# 15_-_MISC_JTAG_HEADERS.net
KiCad netlist of a schematic drawn in Altium Designer
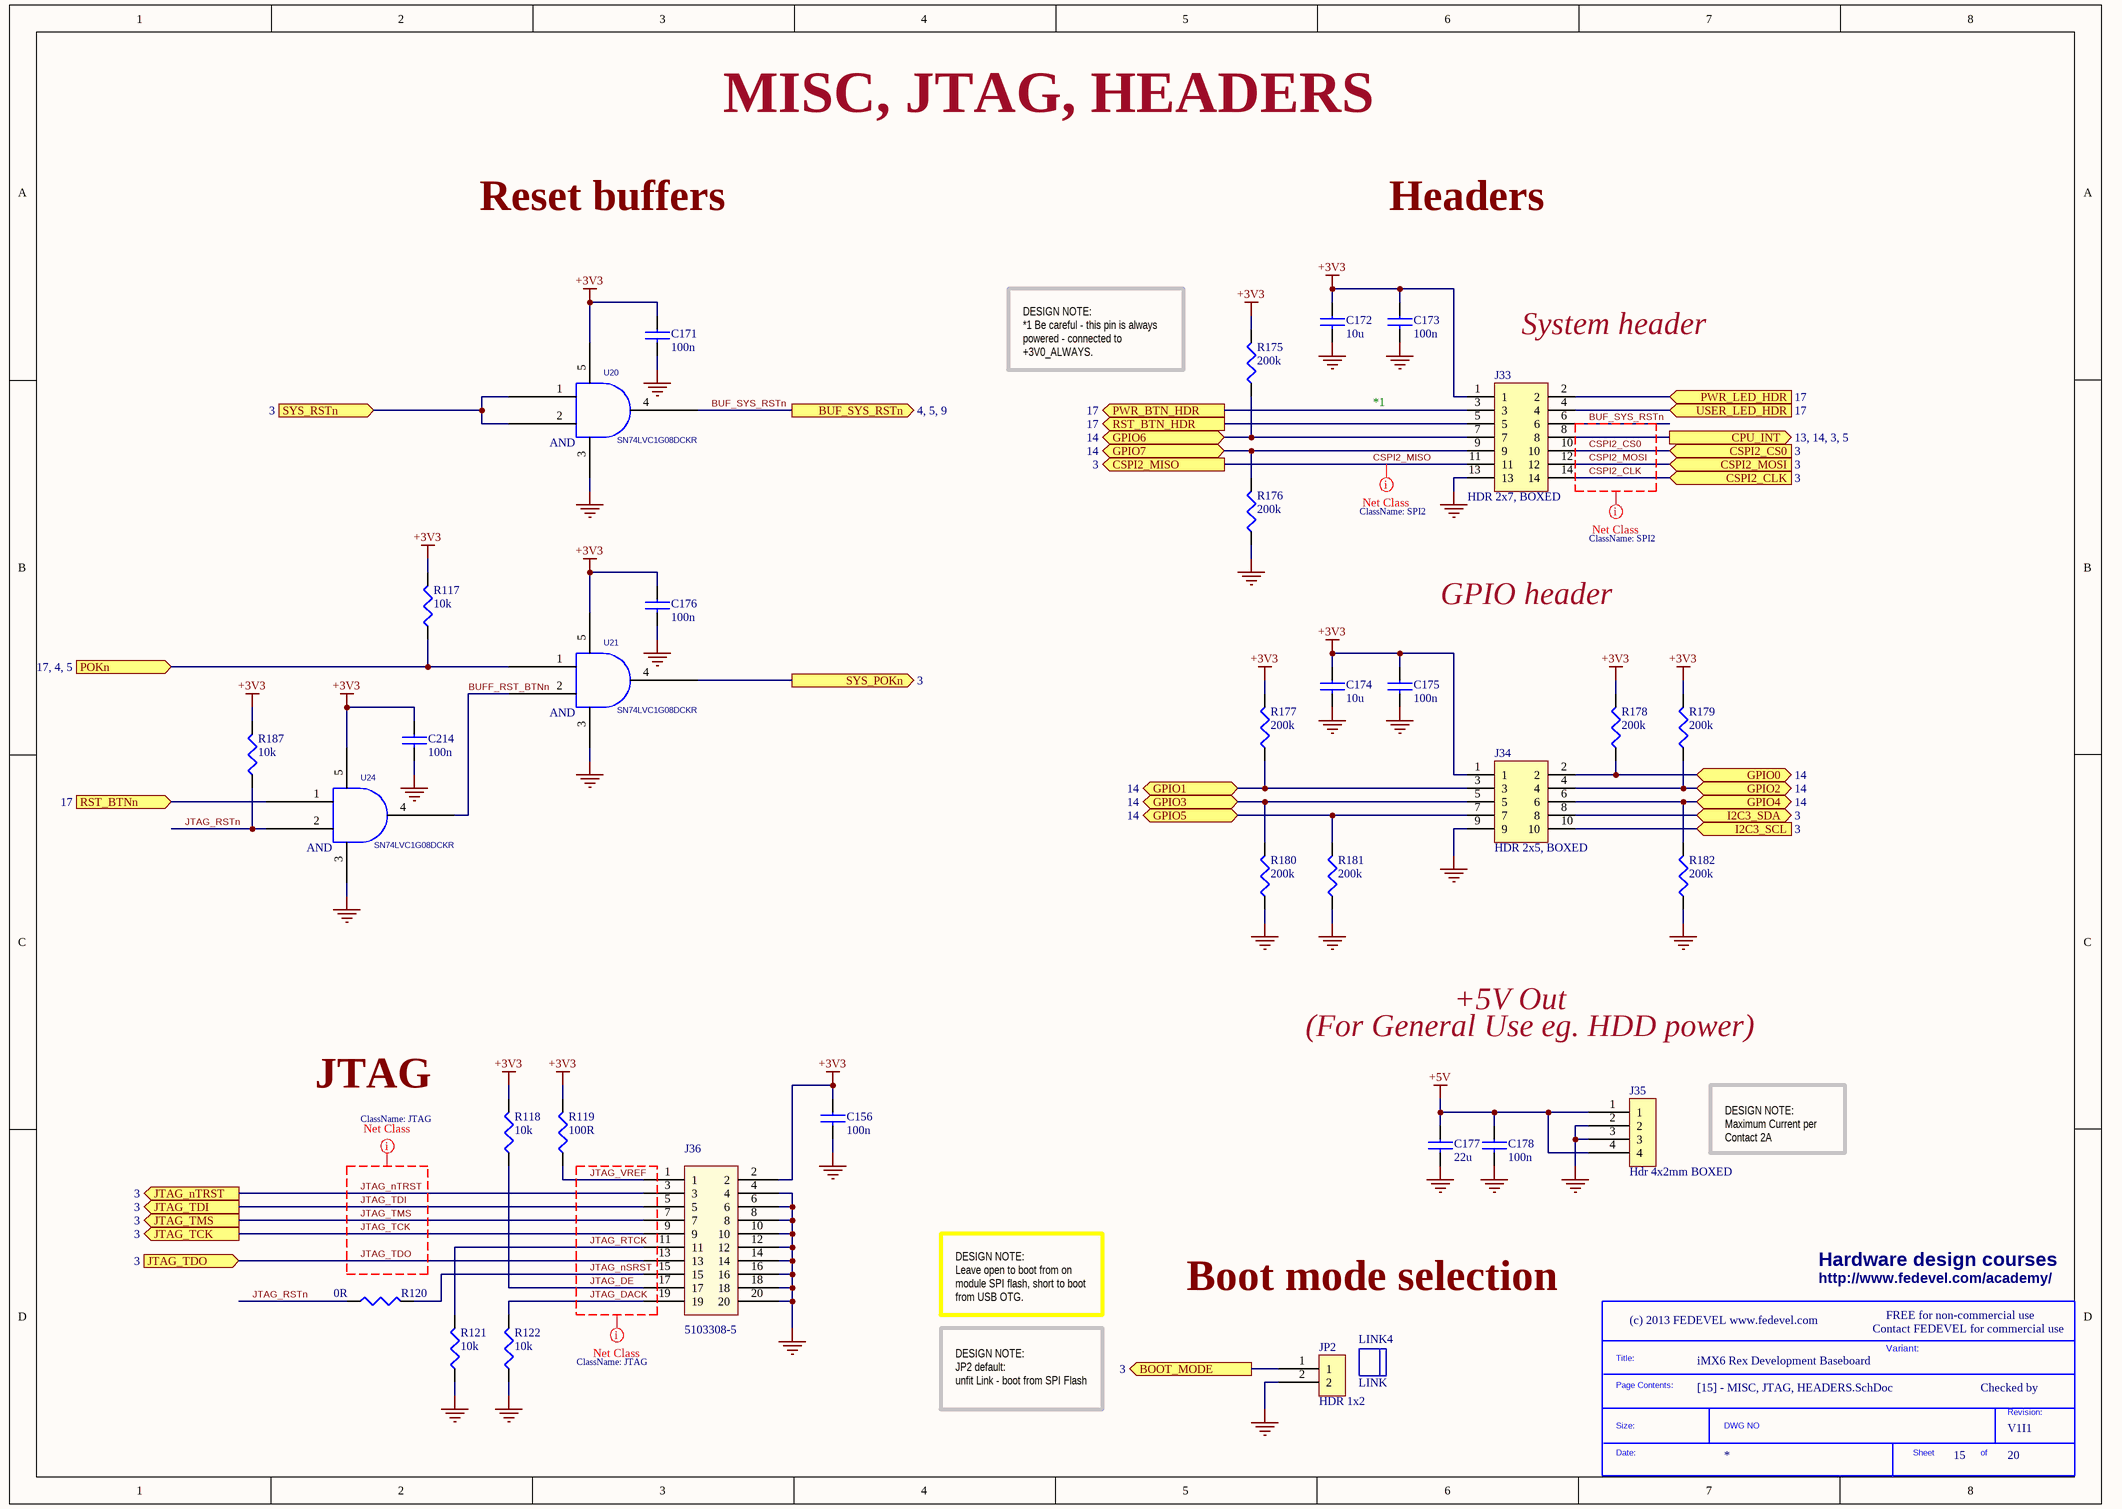
[diagram p0: [15] - MISC, JTAG, HEADERS.SchDoc]

(export (version "E")
  (design (tool "Eeschema 10.0.6"))
  (components
    (comp (ref "C156")
      (value "100n")
      (footprint "C0402")
      (description "CAP CER .10UF 50V X5R 10% 0402")
      (fields
        (field (name "MANUFACTURER") "TDK Corporation")
        (field (name "MANUFACTURER PART NUMBER") "C1005X5R1H104K")
      )
      (libsource (lib "Integrated_Library_RF_FEB_2012") (part "C1005X5R1H104K"))
    )
    (comp (ref "C171")
      (value "100n")
      (footprint "C0402")
      (description "CAP CER .10UF 50V X5R 10% 0402")
      (fields
        (field (name "MANUFACTURER") "TDK Corporation")
        (field (name "MANUFACTURER PART NUMBER") "C1005X5R1H104K")
      )
      (libsource (lib "Integrated_Library_RF_FEB_2012") (part "C1005X5R1H104K"))
    )
    (comp (ref "C172")
      (value "10u")
      (footprint "C0603")
      (description "CAP CER 10UF 6.3V X5R 20% 0603")
      (fields
        (field (name "MANUFACTURER") "TDK Corporation")
        (field (name "MANUFACTURER PART NUMBER") "C1608X5R0J106M")
      )
      (libsource (lib "Integrated_Library_RF_FEB_2012") (part "C1608X5R0J106M"))
    )
    (comp (ref "C173")
      (value "100n")
      (footprint "C0402")
      (description "CAP CER .10UF 50V X5R 10% 0402")
      (fields
        (field (name "MANUFACTURER") "TDK Corporation")
        (field (name "MANUFACTURER PART NUMBER") "C1005X5R1H104K")
      )
      (libsource (lib "Integrated_Library_RF_FEB_2012") (part "C1005X5R1H104K"))
    )
    (comp (ref "C174")
      (value "10u")
      (footprint "C0603")
      (description "CAP CER 10UF 6.3V X5R 20% 0603")
      (fields
        (field (name "MANUFACTURER") "TDK Corporation")
        (field (name "MANUFACTURER PART NUMBER") "C1608X5R0J106M")
      )
      (libsource (lib "Integrated_Library_RF_FEB_2012") (part "C1608X5R0J106M"))
    )
    (comp (ref "C175")
      (value "100n")
      (footprint "C0402")
      (description "CAP CER .10UF 50V X5R 10% 0402")
      (fields
        (field (name "MANUFACTURER") "TDK Corporation")
        (field (name "MANUFACTURER PART NUMBER") "C1005X5R1H104K")
      )
      (libsource (lib "Integrated_Library_RF_FEB_2012") (part "C1005X5R1H104K"))
    )
    (comp (ref "C176")
      (value "100n")
      (footprint "C0402")
      (description "CAP CER .10UF 50V X5R 10% 0402")
      (fields
        (field (name "MANUFACTURER") "TDK Corporation")
        (field (name "MANUFACTURER PART NUMBER") "C1005X5R1H104K")
      )
      (libsource (lib "Integrated_Library_RF_FEB_2012") (part "C1005X5R1H104K"))
    )
    (comp (ref "C177")
      (value "22u")
      (footprint "C0805")
      (description "CAP CER 22UF 16V 10% X5R 0805")
      (fields
        (field (name "MANUFACTURER") "TDK Corporation")
        (field (name "MANUFACTURER PART NUMBER") "C2012X5R1C226K")
        (field (name ".CHECKED PCB") "RF")
        (field (name ".CHECKED SCH") "RF")
      )
      (libsource (lib "Integrated_Library_RF_FEB_2012") (part "C2012X5R1C226K"))
    )
    (comp (ref "C178")
      (value "100n")
      (footprint "C0402")
      (description "CAP CER .10UF 50V X5R 10% 0402")
      (fields
        (field (name "MANUFACTURER") "TDK Corporation")
        (field (name "MANUFACTURER PART NUMBER") "C1005X5R1H104K")
      )
      (libsource (lib "Integrated_Library_RF_FEB_2012") (part "C1005X5R1H104K"))
    )
    (comp (ref "C214")
      (value "100n")
      (footprint "C0402")
      (description "CAP CER .10UF 50V X5R 10% 0402")
      (fields
        (field (name "MANUFACTURER") "TDK Corporation")
        (field (name "MANUFACTURER PART NUMBER") "C1005X5R1H104K")
      )
      (libsource (lib "Integrated_Library_RF_FEB_2012") (part "C1005X5R1H104K"))
    )
    (comp (ref "J33")
      (value "HDR 2x7, BOXED")
      (footprint "HDR_2x7_2.54MM_BOXED")
      (description "CONN HEADER 14POS VERT 10GOLD")
      (fields
        (field (name "MANUFACTURER") "3M")
        (field (name "MANUFACTURER PART NUMBER") "D2514-6002-AR")
        (field (name ".CREATOR") "MM")
        (field (name ".CHECKED PCB") "MM")
        (field (name ".CHECKED SCH") "MM")
      )
      (libsource (lib "Integrated_Library_RF_FEB_2012") (part "D2514-6002-AR"))
    )
    (comp (ref "J34")
      (value "HDR 2x5, BOXED")
      (footprint "HDR_2x5_2.54mm_BOXED")
      (description "CONN HEADER 10POS VERT 10GOLD")
      (fields
        (field (name "MANUFACTURER") "3M")
        (field (name "MANUFACTURER PART NUMBER") "D2510-6002-AR")
        (field (name ".CREATOR") "MM")
        (field (name ".CHECKED PCB") "MM")
        (field (name ".CHECKED SCH") "MM")
      )
      (libsource (lib "Integrated_Library_RF_FEB_2012") (part "D2510-6002-AR"))
    )
    (comp (ref "J35")
      (value "Hdr 4x2mm BOXED")
      (footprint "HDR_1x4_2MM_SHDR")
      (description "CONN HEADER 4POS 2MM VERT TIN")
      (fields
        (field (name "MANUFACTURER") "Molex Inc")
        (field (name "MANUFACTURER PART NUMBER") "0532530470")
        (field (name ".CREATOR") "MM")
        (field (name ".CHECKED PCB") "MM")
        (field (name ".CHECKED SCH") "MM")
      )
      (libsource (lib "Integrated_Library_RF_FEB_2012") (part "0532530470"))
    )
    (comp (ref "J36")
      (value "5103308-5")
      (footprint "HDR_2x10_2.54mm_BOXED")
      (description "CONN HEADER LOPRO STR 20POS GOLD")
      (fields
        (field (name "MANUFACTURER") "TE Connectivity")
        (field (name ".CREATOR") "MM")
        (field (name ".CHECKED PCB") "MM")
        (field (name ".CHECKED SCH") "MM")
      )
      (libsource (lib "Integrated_Library_RF_FEB_2012") (part "5103308-5"))
    )
    (comp (ref "JP2")
      (value "HDR 1x2")
      (footprint "HDR_1x2_2.54MM")
      (description "BERGSTIK II .100\" SR STRAIGHT")
      (fields
        (field (name "MANUFACTURER") "FCI")
        (field (name "MANUFACTURER PART NUMBER") "68001-202HLF")
        (field (name ".CHECKED PCB") "RF")
        (field (name ".CHECKED SCH") "RF")
      )
      (libsource (lib "Integrated_Library_RF_FEB_2012") (part "68001-202HLF"))
    )
    (comp (ref "LINK4")
      (value "LINK")
      (description "CONN JUMPER SHORTING .100\" GOLD")
      (fields
        (field (name "MANUFACTURER") "Sullins Connector Solutions")
        (field (name "MANUFACTURER PART NUMBER") "QPC02SXGN-RC")
        (field (name ".CHECKED SCH") "RF")
      )
      (libsource (lib "Integrated_Library_RF_FEB_2012") (part "QPC02SXGN-RC"))
    )
    (comp (ref "R117")
      (value "10k")
      (footprint "R0402")
      (description "RES 10.0K OHM 1/16W 1% 0402 SMD")
      (fields
        (field (name "MANUFACTURER") "Yageo")
        (field (name "MANUFACTURER PART NUMBER") "RC0402FR-0710KL")
      )
      (libsource (lib "Integrated_Library_RF_FEB_2012") (part "RC0402FR-0710KL"))
    )
    (comp (ref "R118")
      (value "10k")
      (footprint "R0402")
      (description "RES 10.0K OHM 1/16W 1% 0402 SMD")
      (fields
        (field (name "MANUFACTURER") "Yageo")
        (field (name "MANUFACTURER PART NUMBER") "RC0402FR-0710KL")
      )
      (libsource (lib "Integrated_Library_RF_FEB_2012") (part "RC0402FR-0710KL"))
    )
    (comp (ref "R119")
      (value "100R")
      (footprint "R0402")
      (description "RES 100 OHM 1/16W 1% 0402 SMD")
      (fields
        (field (name "MANUFACTURER") "Yageo")
        (field (name "MANUFACTURER PART NUMBER") "RC0402FR-07100RL")
        (field (name ".CHECKED PCB") "RF")
        (field (name ".CHECKED SCH") "RF")
      )
      (libsource (lib "Integrated_Library_RF_FEB_2012") (part "RC0402FR-07100RL"))
    )
    (comp (ref "R120")
      (value "0R")
      (footprint "R0402")
      (description "RES 0.0 OHM 1/16W 0402 SMD")
      (fields
        (field (name "MANUFACTURER") "Yageo")
        (field (name "MANUFACTURER PART NUMBER") "RC0402JR-070RL")
      )
      (libsource (lib "Integrated_Library_RF_FEB_2012") (part "RC0402JR-070RL"))
    )
    (comp (ref "R121")
      (value "10k")
      (footprint "R0402")
      (description "RES 10.0K OHM 1/16W 1% 0402 SMD")
      (fields
        (field (name "MANUFACTURER") "Yageo")
        (field (name "MANUFACTURER PART NUMBER") "RC0402FR-0710KL")
      )
      (libsource (lib "Integrated_Library_RF_FEB_2012") (part "RC0402FR-0710KL"))
    )
    (comp (ref "R122")
      (value "10k")
      (footprint "R0402")
      (description "RES 10.0K OHM 1/16W 1% 0402 SMD")
      (fields
        (field (name "MANUFACTURER") "Yageo")
        (field (name "MANUFACTURER PART NUMBER") "RC0402FR-0710KL")
      )
      (libsource (lib "Integrated_Library_RF_FEB_2012") (part "RC0402FR-0710KL"))
    )
    (comp (ref "R175")
      (value "200k")
      (footprint "R0402")
      (description "RES 200K OHM 1/16W 1% 0402 SMD")
      (fields
        (field (name "MANUFACTURER") "Yageo")
        (field (name "MANUFACTURER PART NUMBER") "RC0402FR-07200KL")
      )
      (libsource (lib "Integrated_Library_RF_FEB_2012") (part "RC0402FR-07200KL"))
    )
    (comp (ref "R176")
      (value "200k")
      (footprint "R0402")
      (description "RES 200K OHM 1/16W 1% 0402 SMD")
      (fields
        (field (name "MANUFACTURER") "Yageo")
        (field (name "MANUFACTURER PART NUMBER") "RC0402FR-07200KL")
      )
      (libsource (lib "Integrated_Library_RF_FEB_2012") (part "RC0402FR-07200KL"))
    )
    (comp (ref "R177")
      (value "200k")
      (footprint "R0402")
      (description "RES 200K OHM 1/16W 1% 0402 SMD")
      (fields
        (field (name "MANUFACTURER") "Yageo")
        (field (name "MANUFACTURER PART NUMBER") "RC0402FR-07200KL")
      )
      (libsource (lib "Integrated_Library_RF_FEB_2012") (part "RC0402FR-07200KL"))
    )
    (comp (ref "R178")
      (value "200k")
      (footprint "R0402")
      (description "RES 200K OHM 1/16W 1% 0402 SMD")
      (fields
        (field (name "MANUFACTURER") "Yageo")
        (field (name "MANUFACTURER PART NUMBER") "RC0402FR-07200KL")
      )
      (libsource (lib "Integrated_Library_RF_FEB_2012") (part "RC0402FR-07200KL"))
    )
    (comp (ref "R179")
      (value "200k")
      (footprint "R0402")
      (description "RES 200K OHM 1/16W 1% 0402 SMD")
      (fields
        (field (name "MANUFACTURER") "Yageo")
        (field (name "MANUFACTURER PART NUMBER") "RC0402FR-07200KL")
      )
      (libsource (lib "Integrated_Library_RF_FEB_2012") (part "RC0402FR-07200KL"))
    )
    (comp (ref "R180")
      (value "200k")
      (footprint "R0402")
      (description "RES 200K OHM 1/16W 1% 0402 SMD")
      (fields
        (field (name "MANUFACTURER") "Yageo")
        (field (name "MANUFACTURER PART NUMBER") "RC0402FR-07200KL")
      )
      (libsource (lib "Integrated_Library_RF_FEB_2012") (part "RC0402FR-07200KL"))
    )
    (comp (ref "R181")
      (value "200k")
      (footprint "R0402")
      (description "RES 200K OHM 1/16W 1% 0402 SMD")
      (fields
        (field (name "MANUFACTURER") "Yageo")
        (field (name "MANUFACTURER PART NUMBER") "RC0402FR-07200KL")
      )
      (libsource (lib "Integrated_Library_RF_FEB_2012") (part "RC0402FR-07200KL"))
    )
    (comp (ref "R182")
      (value "200k")
      (footprint "R0402")
      (description "RES 200K OHM 1/16W 1% 0402 SMD")
      (fields
        (field (name "MANUFACTURER") "Yageo")
        (field (name "MANUFACTURER PART NUMBER") "RC0402FR-07200KL")
      )
      (libsource (lib "Integrated_Library_RF_FEB_2012") (part "RC0402FR-07200KL"))
    )
    (comp (ref "R187")
      (value "10k")
      (footprint "R0402")
      (description "RES 10.0K OHM 1/16W 1% 0402 SMD")
      (fields
        (field (name "MANUFACTURER") "Yageo")
        (field (name "MANUFACTURER PART NUMBER") "RC0402FR-0710KL")
      )
      (libsource (lib "Integrated_Library_RF_FEB_2012") (part "RC0402FR-0710KL"))
    )
    (comp (ref "U20")
      (value "SN74LVC1G08DCKR")
      (footprint "SC70_5")
      (description "SINGLE POSITIVE AND GATE SC-70")
      (fields (field (name "MANUFACTURER") "Texas Instruments"))
      (libsource (lib "Integrated_Library_RF_FEB_2012") (part "SN74LVC1G08DCKR"))
    )
    (comp (ref "U21")
      (value "SN74LVC1G08DCKR")
      (footprint "SC70_5")
      (description "SINGLE POSITIVE AND GATE SC-70")
      (fields (field (name "MANUFACTURER") "Texas Instruments"))
      (libsource (lib "Integrated_Library_RF_FEB_2012") (part "SN74LVC1G08DCKR"))
    )
    (comp (ref "U24")
      (value "SN74LVC1G08DCKR")
      (footprint "SC70_5")
      (description "SINGLE POSITIVE AND GATE SC-70")
      (fields (field (name "MANUFACTURER") "Texas Instruments"))
      (libsource (lib "Integrated_Library_RF_FEB_2012") (part "SN74LVC1G08DCKR"))
    )
  )
  (nets
    (net (code "1") (name "+3V3") (class "Default")
      (node (ref "C156") (pin "1") (pinfunction "1_1") (pintype "passive"))
      (node (ref "C171") (pin "1") (pinfunction "1_1") (pintype "passive"))
      (node (ref "C172") (pin "1") (pinfunction "1_1") (pintype "passive"))
      (node (ref "C173") (pin "1") (pinfunction "1_1") (pintype "passive"))
      (node (ref "C174") (pin "1") (pinfunction "1_1") (pintype "passive"))
      (node (ref "C175") (pin "1") (pinfunction "1_1") (pintype "passive"))
      (node (ref "C176") (pin "1") (pinfunction "1_1") (pintype "passive"))
      (node (ref "C214") (pin "1") (pinfunction "1_1") (pintype "passive"))
      (node (ref "J33") (pin "1") (pinfunction "1_1") (pintype "passive"))
      (node (ref "J34") (pin "1") (pinfunction "1_1") (pintype "passive"))
      (node (ref "J36") (pin "2") (pinfunction "2_2") (pintype "passive"))
      (node (ref "R117") (pin "2") (pinfunction "2_2") (pintype "passive"))
      (node (ref "R118") (pin "2") (pinfunction "2_2") (pintype "passive"))
      (node (ref "R119") (pin "2") (pinfunction "2_2") (pintype "passive"))
      (node (ref "R175") (pin "2") (pinfunction "2_2") (pintype "passive"))
      (node (ref "R177") (pin "2") (pinfunction "2_2") (pintype "passive"))
      (node (ref "R178") (pin "2") (pinfunction "2_2") (pintype "passive"))
      (node (ref "R179") (pin "2") (pinfunction "2_2") (pintype "passive"))
      (node (ref "R187") (pin "2") (pinfunction "2_2") (pintype "passive"))
      (node (ref "U20") (pin "5") (pinfunction "VCC_5") (pintype "power_in"))
      (node (ref "U21") (pin "5") (pinfunction "VCC_5") (pintype "power_in"))
      (node (ref "U24") (pin "5") (pinfunction "VCC_5") (pintype "power_in"))
    )
    (net (code "2") (name "+5V") (class "Default")
      (node (ref "C177") (pin "1") (pinfunction "1_1") (pintype "passive"))
      (node (ref "C178") (pin "1") (pinfunction "1_1") (pintype "passive"))
      (node (ref "J35") (pin "1") (pinfunction "1_1") (pintype "passive"))
      (node (ref "J35") (pin "4") (pinfunction "4_4") (pintype "passive"))
    )
    (net (code "3") (name "/BOOT_MODE") (class "Default")
      (node (ref "JP2") (pin "1") (pinfunction "1_1") (pintype "passive"))
    )
    (net (code "4") (name "/BUFF_RST_BTNn") (class "Default")
      (node (ref "U21") (pin "2") (pinfunction "B_2") (pintype "passive"))
      (node (ref "U24") (pin "4") (pinfunction "Y_4") (pintype "passive"))
    )
    (net (code "5") (name "/BUF_SYS_RSTn") (class "Default")
      (node (ref "J33") (pin "6") (pinfunction "6_6") (pintype "passive"))
      (node (ref "U20") (pin "4") (pinfunction "Y_4") (pintype "passive"))
    )
    (net (code "6") (name "/CPU_INT") (class "Default")
      (node (ref "J33") (pin "8") (pinfunction "8_8") (pintype "passive"))
    )
    (net (code "7") (name "/CSPI2_CLK") (class "Default")
      (node (ref "J33") (pin "14") (pinfunction "14_14") (pintype "passive"))
    )
    (net (code "8") (name "/CSPI2_CS0") (class "Default")
      (node (ref "J33") (pin "10") (pinfunction "10_10") (pintype "passive"))
    )
    (net (code "9") (name "/CSPI2_MISO") (class "Default")
      (node (ref "J33") (pin "11") (pinfunction "11_11") (pintype "passive"))
    )
    (net (code "10") (name "/CSPI2_MOSI") (class "Default")
      (node (ref "J33") (pin "12") (pinfunction "12_12") (pintype "passive"))
    )
    (net (code "11") (name "/GPIO0") (class "Default")
      (node (ref "J34") (pin "2") (pinfunction "2_2") (pintype "passive"))
      (node (ref "R178") (pin "1") (pinfunction "1_1") (pintype "passive"))
    )
    (net (code "12") (name "/GPIO1") (class "Default")
      (node (ref "J34") (pin "3") (pinfunction "3_3") (pintype "passive"))
      (node (ref "R177") (pin "1") (pinfunction "1_1") (pintype "passive"))
    )
    (net (code "13") (name "/GPIO2") (class "Default")
      (node (ref "J34") (pin "4") (pinfunction "4_4") (pintype "passive"))
      (node (ref "R179") (pin "1") (pinfunction "1_1") (pintype "passive"))
    )
    (net (code "14") (name "/GPIO3") (class "Default")
      (node (ref "J34") (pin "5") (pinfunction "5_5") (pintype "passive"))
      (node (ref "R180") (pin "2") (pinfunction "2_2") (pintype "passive"))
    )
    (net (code "15") (name "/GPIO4") (class "Default")
      (node (ref "J34") (pin "6") (pinfunction "6_6") (pintype "passive"))
      (node (ref "R182") (pin "2") (pinfunction "2_2") (pintype "passive"))
    )
    (net (code "16") (name "/GPIO5") (class "Default")
      (node (ref "J34") (pin "7") (pinfunction "7_7") (pintype "passive"))
      (node (ref "R181") (pin "2") (pinfunction "2_2") (pintype "passive"))
    )
    (net (code "17") (name "/GPIO6") (class "Default")
      (node (ref "J33") (pin "7") (pinfunction "7_7") (pintype "passive"))
      (node (ref "R175") (pin "1") (pinfunction "1_1") (pintype "passive"))
    )
    (net (code "18") (name "/GPIO7") (class "Default")
      (node (ref "J33") (pin "9") (pinfunction "9_9") (pintype "passive"))
      (node (ref "R176") (pin "2") (pinfunction "2_2") (pintype "passive"))
    )
    (net (code "19") (name "/I2C3_SCL") (class "Default")
      (node (ref "J34") (pin "10") (pinfunction "10_10") (pintype "passive"))
    )
    (net (code "20") (name "/I2C3_SDA") (class "Default")
      (node (ref "J34") (pin "8") (pinfunction "8_8") (pintype "passive"))
    )
    (net (code "21") (name "/JTAG_DACK") (class "Default")
      (node (ref "J36") (pin "19") (pinfunction "19_19") (pintype "passive"))
      (node (ref "R122") (pin "2") (pinfunction "2_2") (pintype "passive"))
    )
    (net (code "22") (name "/JTAG_DE") (class "Default")
      (node (ref "J36") (pin "17") (pinfunction "17_17") (pintype "passive"))
      (node (ref "R118") (pin "1") (pinfunction "1_1") (pintype "passive"))
    )
    (net (code "23") (name "/JTAG_RSTn") (class "Default")
      (node (ref "R120") (pin "1") (pinfunction "1_1") (pintype "passive"))
      (node (ref "R187") (pin "1") (pinfunction "1_1") (pintype "passive"))
      (node (ref "U24") (pin "2") (pinfunction "B_2") (pintype "passive"))
    )
    (net (code "24") (name "/JTAG_RTCK") (class "Default")
      (node (ref "J36") (pin "11") (pinfunction "11_11") (pintype "passive"))
      (node (ref "R121") (pin "2") (pinfunction "2_2") (pintype "passive"))
    )
    (net (code "25") (name "/JTAG_TCK") (class "Default")
      (node (ref "J36") (pin "9") (pinfunction "9_9") (pintype "passive"))
    )
    (net (code "26") (name "/JTAG_TDI") (class "Default")
      (node (ref "J36") (pin "5") (pinfunction "5_5") (pintype "passive"))
    )
    (net (code "27") (name "/JTAG_TDO") (class "Default")
      (node (ref "J36") (pin "13") (pinfunction "13_13") (pintype "passive"))
    )
    (net (code "28") (name "/JTAG_TMS") (class "Default")
      (node (ref "J36") (pin "7") (pinfunction "7_7") (pintype "passive"))
    )
    (net (code "29") (name "/JTAG_VREF") (class "Default")
      (node (ref "J36") (pin "1") (pinfunction "1_1") (pintype "passive"))
      (node (ref "R119") (pin "1") (pinfunction "1_1") (pintype "passive"))
    )
    (net (code "30") (name "/JTAG_nSRST") (class "Default")
      (node (ref "J36") (pin "15") (pinfunction "15_15") (pintype "passive"))
      (node (ref "R120") (pin "2") (pinfunction "2_2") (pintype "passive"))
    )
    (net (code "31") (name "/JTAG_nTRST") (class "Default")
      (node (ref "J36") (pin "3") (pinfunction "3_3") (pintype "passive"))
    )
    (net (code "32") (name "/POKn") (class "Default")
      (node (ref "R117") (pin "1") (pinfunction "1_1") (pintype "passive"))
      (node (ref "U21") (pin "1") (pinfunction "A_1") (pintype "passive"))
    )
    (net (code "33") (name "/PWR_BTN_HDR") (class "Default")
      (node (ref "J33") (pin "3") (pinfunction "3_3") (pintype "passive"))
    )
    (net (code "34") (name "/PWR_LED_HDR") (class "Default")
      (node (ref "J33") (pin "2") (pinfunction "2_2") (pintype "passive"))
    )
    (net (code "35") (name "/RST_BTN_HDR") (class "Default")
      (node (ref "J33") (pin "5") (pinfunction "5_5") (pintype "passive"))
    )
    (net (code "36") (name "/RST_BTNn") (class "Default")
      (node (ref "U24") (pin "1") (pinfunction "A_1") (pintype "passive"))
    )
    (net (code "37") (name "/SYS_POKn") (class "Default")
      (node (ref "U21") (pin "4") (pinfunction "Y_4") (pintype "passive"))
    )
    (net (code "38") (name "/SYS_RSTn") (class "Default")
      (node (ref "U20") (pin "1") (pinfunction "A_1") (pintype "passive"))
      (node (ref "U20") (pin "2") (pinfunction "B_2") (pintype "passive"))
    )
    (net (code "39") (name "/USER_LED_HDR") (class "Default")
      (node (ref "J33") (pin "4") (pinfunction "4_4") (pintype "passive"))
    )
    (net (code "40") (name "GND") (class "Default")
      (node (ref "C156") (pin "2") (pinfunction "2_2") (pintype "passive"))
      (node (ref "C171") (pin "2") (pinfunction "2_2") (pintype "passive"))
      (node (ref "C172") (pin "2") (pinfunction "2_2") (pintype "passive"))
      (node (ref "C173") (pin "2") (pinfunction "2_2") (pintype "passive"))
      (node (ref "C174") (pin "2") (pinfunction "2_2") (pintype "passive"))
      (node (ref "C175") (pin "2") (pinfunction "2_2") (pintype "passive"))
      (node (ref "C176") (pin "2") (pinfunction "2_2") (pintype "passive"))
      (node (ref "C177") (pin "2") (pinfunction "2_2") (pintype "passive"))
      (node (ref "C178") (pin "2") (pinfunction "2_2") (pintype "passive"))
      (node (ref "C214") (pin "2") (pinfunction "2_2") (pintype "passive"))
      (node (ref "J33") (pin "13") (pinfunction "13_13") (pintype "passive"))
      (node (ref "J34") (pin "9") (pinfunction "9_9") (pintype "passive"))
      (node (ref "J35") (pin "2") (pinfunction "2_2") (pintype "passive"))
      (node (ref "J35") (pin "3") (pinfunction "3_3") (pintype "passive"))
      (node (ref "J36") (pin "10") (pinfunction "10_10") (pintype "passive"))
      (node (ref "J36") (pin "12") (pinfunction "12_12") (pintype "passive"))
      (node (ref "J36") (pin "14") (pinfunction "14_14") (pintype "passive"))
      (node (ref "J36") (pin "16") (pinfunction "16_16") (pintype "passive"))
      (node (ref "J36") (pin "18") (pinfunction "18_18") (pintype "passive"))
      (node (ref "J36") (pin "20") (pinfunction "20_20") (pintype "passive"))
      (node (ref "J36") (pin "4") (pinfunction "4_4") (pintype "passive"))
      (node (ref "J36") (pin "6") (pinfunction "6_6") (pintype "passive"))
      (node (ref "J36") (pin "8") (pinfunction "8_8") (pintype "passive"))
      (node (ref "JP2") (pin "2") (pinfunction "2_2") (pintype "passive"))
      (node (ref "R121") (pin "1") (pinfunction "1_1") (pintype "passive"))
      (node (ref "R122") (pin "1") (pinfunction "1_1") (pintype "passive"))
      (node (ref "R176") (pin "1") (pinfunction "1_1") (pintype "passive"))
      (node (ref "R180") (pin "1") (pinfunction "1_1") (pintype "passive"))
      (node (ref "R181") (pin "1") (pinfunction "1_1") (pintype "passive"))
      (node (ref "R182") (pin "1") (pinfunction "1_1") (pintype "passive"))
      (node (ref "U20") (pin "3") (pinfunction "GND_3") (pintype "power_in"))
      (node (ref "U21") (pin "3") (pinfunction "GND_3") (pintype "power_in"))
      (node (ref "U24") (pin "3") (pinfunction "GND_3") (pintype "power_in"))
    )
  )
)
